# NanoPiAir_SDR_Shield_V1.net
KiCad netlist of a schematic drawn in Altium Designer
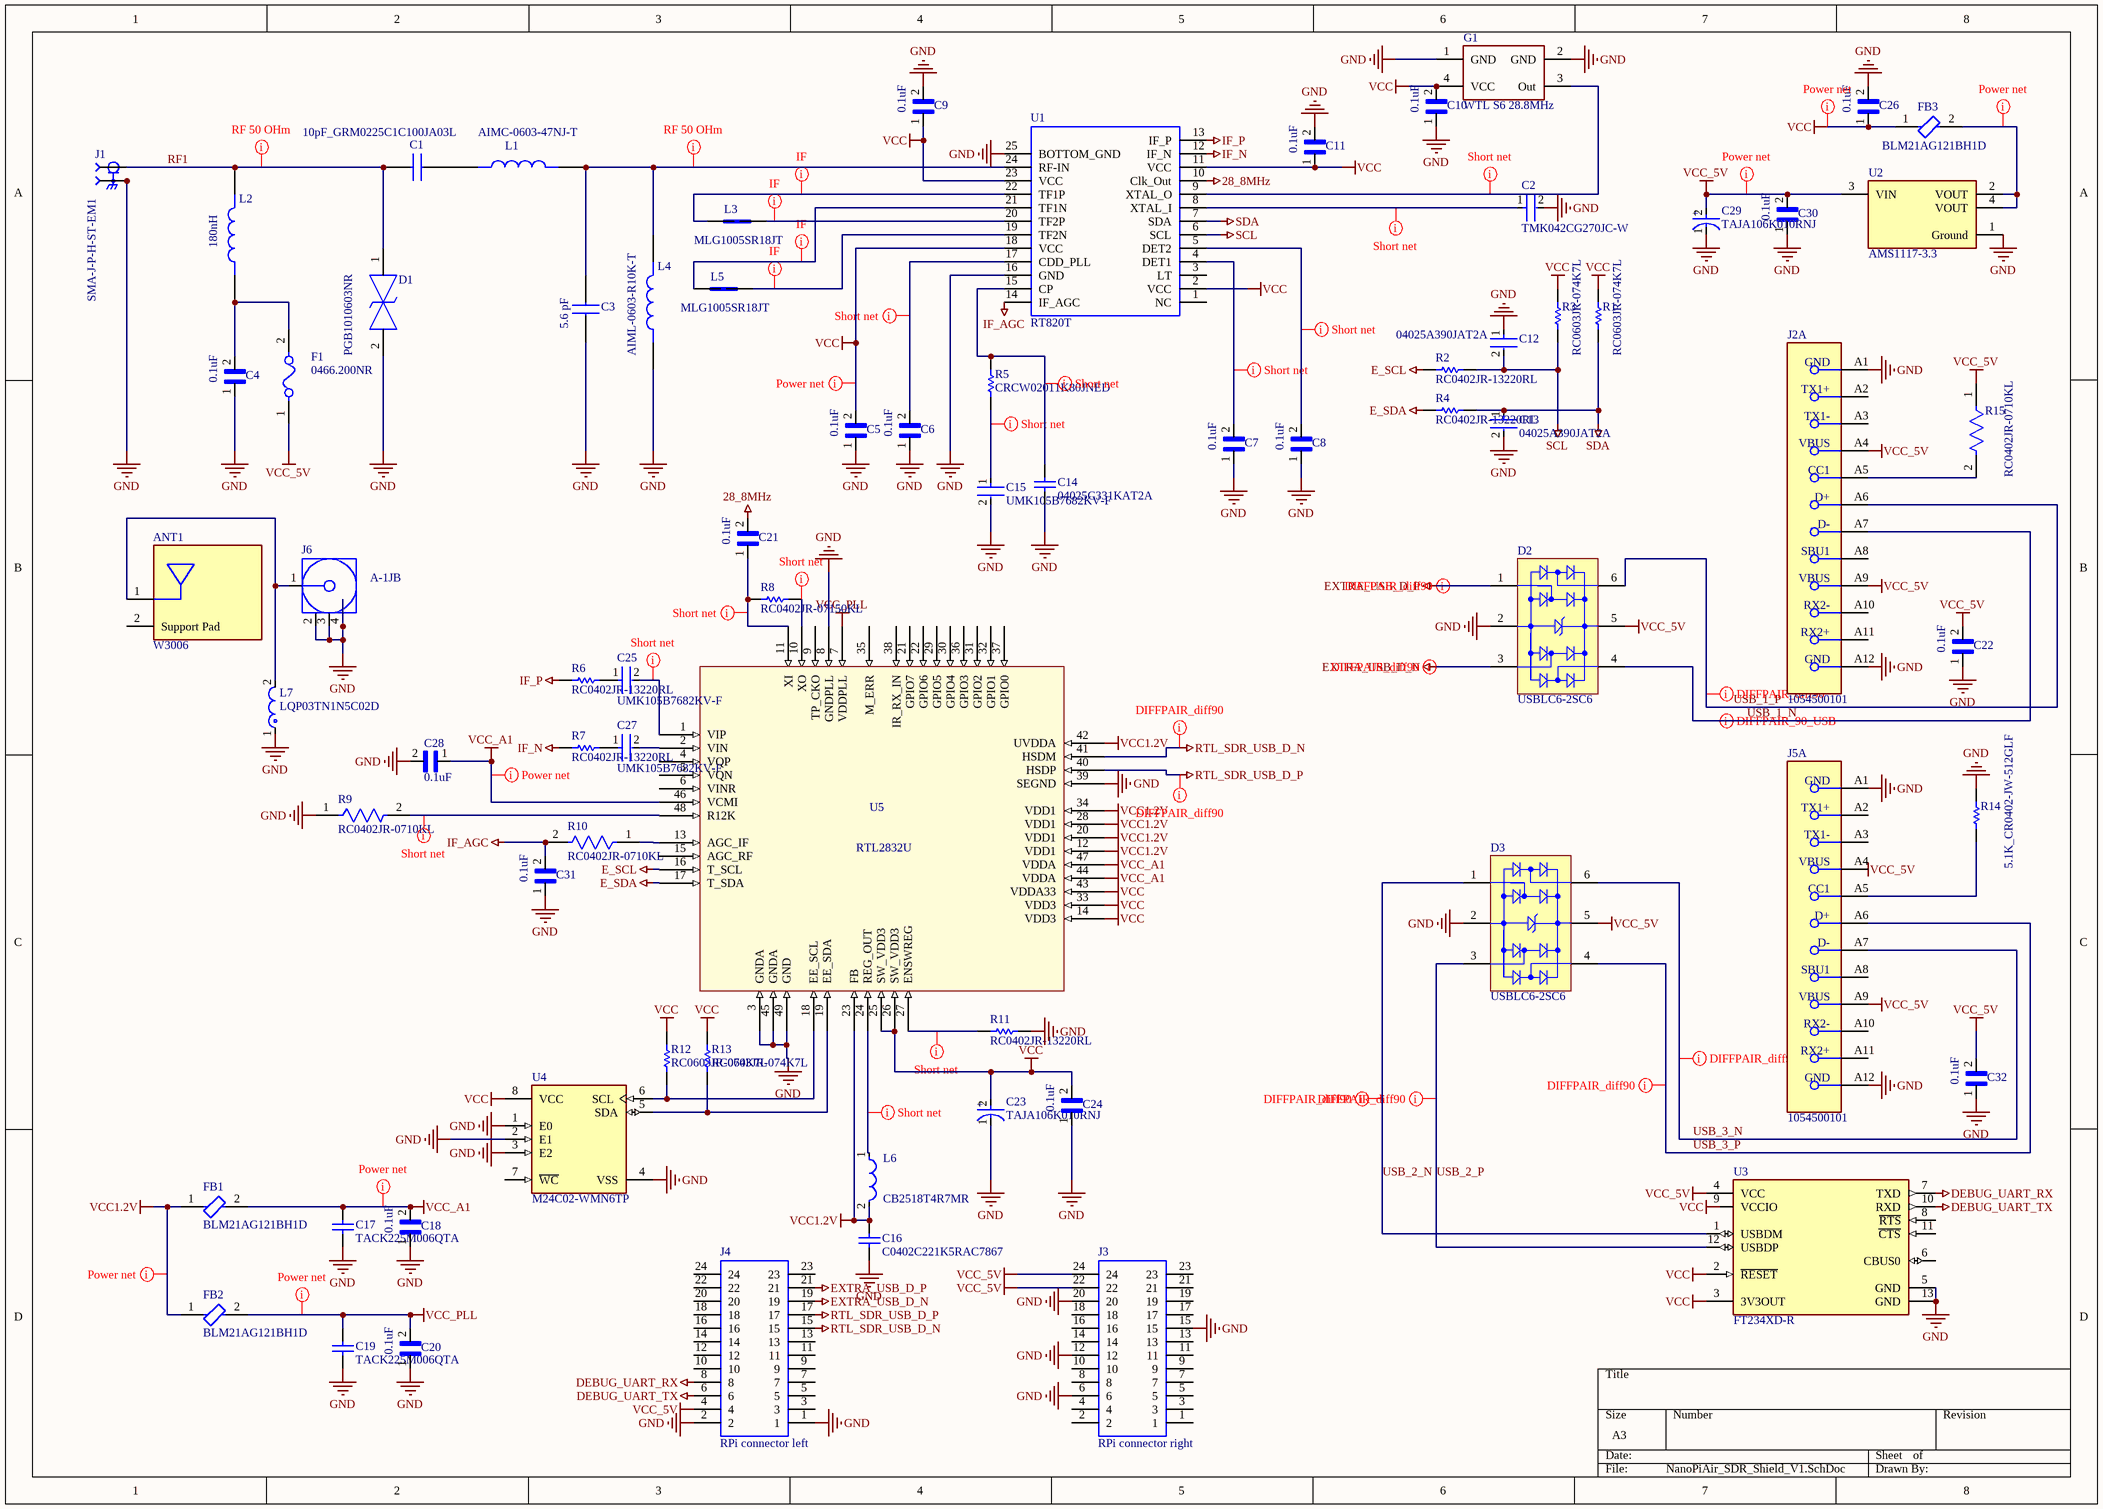
[diagram p0: NanoPiAir_SDR_Shield_V1.SchDoc]

(export (version "E")
  (design (tool "Eeschema 10.0.6"))
  (components
    (comp (ref "ANT1")
      (value "W3006")
      (footprint "FP-W3006-0")
      (description "RF ANT 2.4GHZ/5.5GHZ CHIP SLD")
      (libsource (lib "Altium Content Vault") (part "7e9f1c3ea5b015cef85830d8f377364"))
    )
    (comp (ref "C1")
      (value "10pF_GRM0225C1C100JA03L")
      (footprint "CAPC0402X22N")
      (description "Cap Ceramic 10pF 16V C0G 5% Pad SMD 01005 125C T/R")
      (fields
        (field (name "MOUSER PART NUMBER") "81-GRM0225C1C100JA3L")
        (field (name "MANUFACTURER_PART_NUMBER") "GRM0225C1C100JA03L")
      )
      (libsource (lib "Schlib1") (part "GRM0225C1C100JA03L"))
    )
    (comp (ref "C2")
      (value "TMK042CG270JC-W")
      (footprint "FP-01005-L_0_4_0_02-W_0_2-MFG")
      (description "None")
      (libsource (lib "Schlib1") (part "CMP-14477-000467-2"))
    )
    (comp (ref "C3")
      (value "5.6 pF")
      (footprint "C0603")
      (fields
        (field (name "MOUSER PART NUMBER") "80-C0603C569C5G")
        (field (name "MANUFACTURER_PART_NUMBER") "C0603C569C5GACTU")
      )
      (libsource (lib "Schlib1") (part "C0603C569C5GACTU"))
    )
    (comp (ref "C4")
      (value "0.1uF")
      (footprint "CAPC1005X55N")
      (fields (field (name "MP") "LMF105B7104KVHF"))
      (libsource (lib "Schlib1") (part "LMF105B7104KVHF"))
    )
    (comp (ref "C5")
      (value "0.1uF")
      (footprint "CAPC1005X55N")
      (fields (field (name "MP") "LMF105B7104KVHF"))
      (libsource (lib "Schlib1") (part "LMF105B7104KVHF"))
    )
    (comp (ref "C6")
      (value "0.1uF")
      (footprint "CAPC1005X55N")
      (fields (field (name "MP") "LMF105B7104KVHF"))
      (libsource (lib "Schlib1") (part "LMF105B7104KVHF"))
    )
    (comp (ref "C7")
      (value "0.1uF")
      (footprint "CAPC1005X55N")
      (fields (field (name "MP") "LMF105B7104KVHF"))
      (libsource (lib "Schlib1") (part "LMF105B7104KVHF"))
    )
    (comp (ref "C8")
      (value "0.1uF")
      (footprint "CAPC1005X55N")
      (fields (field (name "MP") "LMF105B7104KVHF"))
      (libsource (lib "Schlib1") (part "LMF105B7104KVHF"))
    )
    (comp (ref "C9")
      (value "0.1uF")
      (footprint "CAPC1005X55N")
      (fields (field (name "MP") "LMF105B7104KVHF"))
      (libsource (lib "Schlib1") (part "LMF105B7104KVHF"))
    )
    (comp (ref "C10")
      (value "0.1uF")
      (footprint "CAPC1005X55N")
      (fields (field (name "MP") "LMF105B7104KVHF"))
      (libsource (lib "Schlib1") (part "LMF105B7104KVHF"))
    )
    (comp (ref "C11")
      (value "0.1uF")
      (footprint "CAPC1005X55N")
      (fields (field (name "MP") "LMF105B7104KVHF"))
      (libsource (lib "Schlib1") (part "LMF105B7104KVHF"))
    )
    (comp (ref "C12")
      (value "04025A390JAT2A")
      (footprint "FP-0402-L_1_0_1-W_0_5_0_1-IPC_B")
      (description "General Purpose Ceramic Capacitor, 0402, 39pF, 5%, C0G, 30ppm/°C, 50V")
      (fields (field (name "TOLERANCE") "5%") (field (name "VOLTAGE") "50V"))
      (libsource (lib "Altium Content Vault") (part "b4654b650e69147ec39a6b967a45e02"))
    )
    (comp (ref "C13")
      (value "04025A390JAT2A")
      (footprint "FP-0402-L_1_0_1-W_0_5_0_1-IPC_B")
      (description "General Purpose Ceramic Capacitor, 0402, 39pF, 5%, C0G, 30ppm/°C, 50V")
      (fields (field (name "TOLERANCE") "5%") (field (name "VOLTAGE") "50V"))
      (libsource (lib "Altium Content Vault") (part "b4654b650e69147ec39a6b967a45e02"))
    )
    (comp (ref "C14")
      (value "04025C331KAT2A")
      (footprint "CAPC1005X56X25NL10T15")
      (fields (field (name "MANUFACTURER") "AVX Interconnect / Elco"))
      (libsource (lib "Altium Content Vault") (part "CAP"))
    )
    (comp (ref "C15")
      (value "UMK105B7682KV-F")
      (footprint "FP-0402-L_1_0_0_05-W_0_5-IPC_C")
      (description "None")
      (fields (field (name "TOLERANCE") "10%") (field (name "VOLTAGE") "50V"))
      (libsource (lib "Altium Content Vault") (part "b4654b650e69147ec39a6b967a45e02"))
    )
    (comp (ref "C16")
      (value "C0402C221K5RAC7867")
      (footprint "CAPC1005X60X30NL05T10")
      (fields (field (name "MANUFACTURER") "Kemet"))
      (libsource (lib "Altium Content Vault") (part "CAP"))
    )
    (comp (ref "C17")
      (value "TACK225M006QTA")
      (footprint "CAPC1005X70X10NL20T00")
      (fields (field (name "MANUFACTURER") "AVX Interconnect / Elco"))
      (libsource (lib "Altium Content Vault") (part "CAP"))
    )
    (comp (ref "C18")
      (value "0.1uF")
      (footprint "CAPC1005X55N")
      (fields (field (name "MP") "LMF105B7104KVHF"))
      (libsource (lib "Schlib1") (part "LMF105B7104KVHF"))
    )
    (comp (ref "C19")
      (value "TACK225M006QTA")
      (footprint "CAPC1005X70X10NL20T00")
      (fields (field (name "MANUFACTURER") "AVX Interconnect / Elco"))
      (libsource (lib "Altium Content Vault") (part "CAP"))
    )
    (comp (ref "C20")
      (value "0.1uF")
      (footprint "CAPC1005X55N")
      (fields (field (name "MP") "LMF105B7104KVHF"))
      (libsource (lib "Schlib1") (part "LMF105B7104KVHF"))
    )
    (comp (ref "C21")
      (value "0.1uF")
      (footprint "CAPC1005X55N")
      (fields (field (name "MP") "LMF105B7104KVHF"))
      (libsource (lib "Schlib1") (part "LMF105B7104KVHF"))
    )
    (comp (ref "C22")
      (value "0.1uF")
      (footprint "CAPC1005X55N")
      (fields (field (name "MP") "LMF105B7104KVHF"))
      (libsource (lib "Schlib1") (part "LMF105B7104KVHF"))
    )
    (comp (ref "C23")
      (value "TAJA106K010RNJ")
      (footprint "FP-TAJA-MFG")
      (description "10uF 10V  ±10% 3Ω 1206  SMD Tantalum Capacitor")
      (fields (field (name "TOLERANCE") "10%") (field (name "VOLTAGE") "10V"))
      (libsource (lib "Altium Content Vault") (part "203bc49f2ac43e59fd269a8c329ed05"))
    )
    (comp (ref "C24")
      (value "0.1uF")
      (footprint "CAPC1005X55N")
      (fields (field (name "MP") "LMF105B7104KVHF"))
      (libsource (lib "Schlib1") (part "LMF105B7104KVHF"))
    )
    (comp (ref "C25")
      (value "UMK105B7682KV-F")
      (footprint "FP-0402-L_1_0_0_05-W_0_5-IPC_C")
      (description "None")
      (fields (field (name "TOLERANCE") "10%") (field (name "VOLTAGE") "50V"))
      (libsource (lib "Altium Content Vault") (part "b4654b650e69147ec39a6b967a45e02"))
    )
    (comp (ref "C26")
      (value "0.1uF")
      (footprint "CAPC1005X55N")
      (fields (field (name "MP") "LMF105B7104KVHF"))
      (libsource (lib "Schlib1") (part "LMF105B7104KVHF"))
    )
    (comp (ref "C27")
      (value "UMK105B7682KV-F")
      (footprint "FP-0402-L_1_0_0_05-W_0_5-IPC_C")
      (description "None")
      (fields (field (name "TOLERANCE") "10%") (field (name "VOLTAGE") "50V"))
      (libsource (lib "Altium Content Vault") (part "b4654b650e69147ec39a6b967a45e02"))
    )
    (comp (ref "C28")
      (value "0.1uF")
      (footprint "CAPC1005X55N")
      (fields (field (name "MP") "LMF105B7104KVHF"))
      (libsource (lib "") (part "LMF105B7104KVHF_1"))
    )
    (comp (ref "C29")
      (value "TAJA106K010RNJ")
      (footprint "FP-TAJA-MFG")
      (description "10uF 10V  ±10% 3Ω 1206  SMD Tantalum Capacitor")
      (fields (field (name "TOLERANCE") "10%") (field (name "VOLTAGE") "10V"))
      (libsource (lib "Altium Content Vault") (part "203bc49f2ac43e59fd269a8c329ed05"))
    )
    (comp (ref "C30")
      (value "0.1uF")
      (footprint "CAPC1005X55N")
      (fields (field (name "MP") "LMF105B7104KVHF"))
      (libsource (lib "Schlib1") (part "LMF105B7104KVHF"))
    )
    (comp (ref "C31")
      (value "0.1uF")
      (footprint "CAPC1005X55N")
      (fields (field (name "MP") "LMF105B7104KVHF"))
      (libsource (lib "Schlib1") (part "LMF105B7104KVHF"))
    )
    (comp (ref "C32")
      (value "0.1uF")
      (footprint "CAPC1005X55N")
      (fields (field (name "MP") "LMF105B7104KVHF"))
      (libsource (lib "Schlib1") (part "LMF105B7104KVHF"))
    )
    (comp (ref "D1")
      (value "PGB1010603NR")
      (footprint "PGB1010603MR")
      (description "ESD Suppressors / TVS Diodes 0603 24VDC .06pF")
      (fields (field (name "MOUSER PART NUMBER") "576-PGB1010603NR"))
      (libsource (lib "Schlib1") (part "PGB1010603NR"))
    )
    (comp (ref "D2")
      (value "USBLC6-2SC6")
      (footprint "STM-SOT23-6L_V")
      (description "Very low capacitance ESD protection, 3.5 pF, -40 to 125 degC, 6-Pin SOT23, RoHS, Tape and Reel")
      (fields (field (name "MANUFACTURER") "STMicroelectronics"))
      (libsource (lib "Altium Content Vault") (part "STM-USB_DVI_HDMIULC6-4SC6X-SOT23-6L"))
    )
    (comp (ref "D3")
      (value "USBLC6-2SC6")
      (footprint "STM-SOT23-6L_V")
      (description "Very low capacitance ESD protection, 3.5 pF, -40 to 125 degC, 6-Pin SOT23, RoHS, Tape and Reel")
      (fields (field (name "MANUFACTURER") "STMicroelectronics"))
      (libsource (lib "Altium Content Vault") (part "STM-USB_DVI_HDMIULC6-4SC6X-SOT23-6L"))
    )
    (comp (ref "F1")
      (value "0466.200NR")
      (footprint "FP-0466-MFG")
      (description "FUSE BOARD MNT 200MA 125VAC/VDC")
      (libsource (lib "Altium Content Vault") (part "5bcf9b9f640e542cf0359d10258e979"))
    )
    (comp (ref "FB1")
      (value "BLM21AG121BH1D")
      (footprint "FP-BLM21-0_2-t0_85-e0_5-IPC_B")
      (description "Chip Ferrite Bead, 0805, 120Ω @ 100MHz, 0.09Ω, 25%, 1A")
      (libsource (lib "Altium Content Vault") (part "5f30dd21d616792df468990f7003faa"))
    )
    (comp (ref "FB2")
      (value "BLM21AG121BH1D")
      (footprint "FP-BLM21-0_2-t0_85-e0_5-IPC_B")
      (description "Chip Ferrite Bead, 0805, 120Ω @ 100MHz, 0.09Ω, 25%, 1A")
      (libsource (lib "Altium Content Vault") (part "5f30dd21d616792df468990f7003faa"))
    )
    (comp (ref "FB3")
      (value "BLM21AG121BH1D")
      (footprint "FP-BLM21-0_2-t0_85-e0_5-IPC_B")
      (description "Chip Ferrite Bead, 0805, 120Ω @ 100MHz, 0.09Ω, 25%, 1A")
      (libsource (lib "Altium Content Vault") (part "5f30dd21d616792df468990f7003faa"))
    )
    (comp (ref "G1")
      (value "WTL S6 28.8MHz")
      (footprint "XTAL_RTL_SDR(CHINA_WTL_S6)")
      (description "28.2 MHz Â±1ppm Generator")
      (fields (field (name "MF") "ECS Inc.") (field (name "DIGI-KEY_PART_NUMBER") "XC2021-2-ND"))
      (libsource (lib "Schlib1") (part "WTL S6 28.8MHz"))
    )
    (comp (ref "J1")
      (value "SMA-J-P-H-ST-EM1")
      (footprint "SAMTEC_SMA-J-P-H-ST-EM1")
      (description "SMA Connector Jack, Female Socket 50Ohm Board Edge, End Launch Solder")
      (libsource (lib "Schlib1") (part "SMA-J-P-H-ST-EM1"))
    )
    (comp (ref "J2")
      (value "1054500101")
      (footprint "FP-1054500101-MFG")
      (description "CONN RCP USB3.1 TYPEC 24P SMD RA")
      (fields
        (field (name "MANUFACTURER") "Molex")
        (field (name "OCTOPART") "https://octopart.com/105450-0101-molex-68082325")
      )
      (libsource (lib "Altium Content Vault") (part "9808b19ecaf079fb99eed69f0495cd0"))
    )
    (comp (ref "J3")
      (value "RPi connector right")
      (footprint "RHDR24W77P254X254_2X12_3048X503X673P")
      (description "Headers & Wire Housings RECEPT 24POS .100 VERT DUAL")
      (fields
        (field (name "MOUSER PART NUMBER") "571-6-534998-2")
        (field (name "MANUFACTURER_PART_NUMBER") "6-534998-2")
      )
      (libsource (lib "Schlib1") (part "6-534998-2"))
    )
    (comp (ref "J4")
      (value "RPi connector left")
      (footprint "RHDR24W77P254X254_2X12_3048X503X673P")
      (description "Headers & Wire Housings RECEPT 24POS .100 VERT DUAL")
      (fields
        (field (name "MOUSER PART NUMBER") "571-6-534998-2")
        (field (name "MANUFACTURER_PART_NUMBER") "6-534998-2")
      )
      (libsource (lib "Schlib1") (part "6-534998-2"))
    )
    (comp (ref "J5")
      (value "1054500101")
      (footprint "FP-1054500101-MFG")
      (description "CONN RCP USB3.1 TYPEC 24P SMD RA")
      (fields
        (field (name "MANUFACTURER") "Molex")
        (field (name "OCTOPART") "https://octopart.com/105450-0101-molex-68082325")
      )
      (libsource (lib "Altium Content Vault") (part "9808b19ecaf079fb99eed69f0495cd0"))
    )
    (comp (ref "J6")
      (value "A-1JB")
      (footprint "AMPH-A-1JB_V")
      (description "AMC PCB Jack, 0 to 60 GHz, 60 V, -40 to 90 degC, 4-Pin SMD, RoHS, Tape and Reel")
      (fields (field (name "TOLERANCE") "10%"))
      (libsource (lib "Altium Content Vault") (part "CN-S-3F-RF4"))
    )
    (comp (ref "L1")
      (value "AIMC-0603-47NJ-T")
      (footprint "INDC1608X95N")
      (description "IND 47nH 0.3A 700mâ„¦")
      (fields (field (name "MF") "Abracon"))
      (libsource (lib "Schlib1") (part "AIMC-0603-47NJ-T"))
    )
    (comp (ref "L2")
      (value "180nH")
      (footprint "INDC1608X95N")
      (description "IND 0.18uH 0.05A 600mâ„¦")
      (fields (field (name "MP") "AIML-0603-R18K-T") (field (name "MF") "Abracon"))
      (libsource (lib "Schlib1") (part "AIML-0603-R18K-T"))
    )
    (comp (ref "L3")
      (value "MLG1005SR18JT")
      (footprint "CAPC1005X55N")
      (description "Ind High Frequency Chip Unshielded Multi-Layer 180nH 5% 100MHz 8Q-Factor Ceramic 150mA 0402 T/R")
      (libsource (lib "Schlib1") (part "MLG1005SR18JT"))
    )
    (comp (ref "L4")
      (value "AIML-0603-R10K-T")
      (footprint "INDC1608X95N")
      (description "100 nH Shielded Multilayer Inductor 50 mA 500mOhm Max 0603 (1608 Metric)")
      (fields (field (name "MF") "Abracon"))
      (libsource (lib "Schlib1") (part "AIML-0603-R10K-T"))
    )
    (comp (ref "L5")
      (value "MLG1005SR18JT")
      (footprint "CAPC1005X55N")
      (description "Ind High Frequency Chip Unshielded Multi-Layer 180nH 5% 100MHz 8Q-Factor Ceramic 150mA 0402 T/R")
      (libsource (lib "Schlib1") (part "MLG1005SR18JT"))
    )
    (comp (ref "L6")
      (value "CB2518T4R7MR")
      (footprint "FP-CB2518-IPC_B")
      (description "SMD Inductors 4.7uH ±20% 1.2A 0.13Ω 1007")
      (fields (field (name "TOLERANCE") "20%"))
      (libsource (lib "Altium Content Vault") (part "725321dda6339637d4d059423bc1c3c"))
    )
    (comp (ref "L7")
      (value "LQP03TN1N5C02D")
      (footprint "FP-LQP03TG_02-IPC_A")
      (description "Film type RF Inductor 1.5nH ±0.2nH 600mA 0.15Ω 0201 (0603)")
      (libsource (lib "Altium Content Vault") (part "4cc4b267dca4c8e51f7102f422741d8"))
    )
    (comp (ref "R1")
      (value "RC0603JR-074K7L")
      (footprint "RESC1608X55X25ML10T15")
      (description "Chip Resistor, 4.7 KOhm, +/- 5%, 100 mW, -55 to 155 degC, 0603 (1608 Metric), RoHS, Tape and Reel")
      (fields (field (name "TOLERANCE") "5%") (field (name "MANUFACTURER") "Yageo"))
      (libsource (lib "Altium Content Vault") (part "RES-2"))
    )
    (comp (ref "R2")
      (value "RC0402JR-13220RL")
      (footprint "RESC1005X40X25ML05T10")
      (fields (field (name "MANUFACTURER") "Yageo"))
      (libsource (lib "Altium Content Vault") (part "RES"))
    )
    (comp (ref "R3")
      (value "RC0603JR-074K7L")
      (footprint "RESC1608X55X25ML10T15")
      (description "Chip Resistor, 4.7 KOhm, +/- 5%, 100 mW, -55 to 155 degC, 0603 (1608 Metric), RoHS, Tape and Reel")
      (fields (field (name "TOLERANCE") "5%") (field (name "MANUFACTURER") "Yageo"))
      (libsource (lib "Altium Content Vault") (part "RES-2"))
    )
    (comp (ref "R4")
      (value "RC0402JR-13220RL")
      (footprint "RESC1005X40X25ML05T10")
      (fields (field (name "MANUFACTURER") "Yageo"))
      (libsource (lib "Altium Content Vault") (part "RES"))
    )
    (comp (ref "R5")
      (value "CRCW02011K80JNED")
      (footprint "RESC0603X28X15LL05T05")
      (fields (field (name "MANUFACTURER") "Vishay Dale"))
      (libsource (lib "Altium Content Vault") (part "RES"))
    )
    (comp (ref "R6")
      (value "RC0402JR-13220RL")
      (footprint "RESC1005X40X25ML05T10")
      (fields (field (name "MANUFACTURER") "Yageo"))
      (libsource (lib "Altium Content Vault") (part "RES"))
    )
    (comp (ref "R7")
      (value "RC0402JR-13220RL")
      (footprint "RESC1005X40X25ML05T10")
      (fields (field (name "MANUFACTURER") "Yageo"))
      (libsource (lib "Altium Content Vault") (part "RES"))
    )
    (comp (ref "R8")
      (value "RC0402JR-07150KL")
      (footprint "RESC1005X40X25ML05T10")
      (fields (field (name "MANUFACTURER") "Yageo / Phycomp"))
      (libsource (lib "Altium Content Vault") (part "RES"))
    )
    (comp (ref "R9")
      (value "RC0402JR-0710KL")
      (footprint "FP-RC0402-0_4-IPC_C")
      (description "RES 10K OHM 5% 1/16W 0402")
      (fields (field (name "TOLERANCE") "5%"))
      (libsource (lib "Altium Content Vault") (part "1029c3af85768c4190bb7ad29bc67b5"))
    )
    (comp (ref "R10")
      (value "RC0402JR-0710KL")
      (footprint "FP-RC0402-0_4-IPC_C")
      (description "RES 10K OHM 5% 1/16W 0402")
      (fields (field (name "TOLERANCE") "5%"))
      (libsource (lib "Altium Content Vault") (part "1029c3af85768c4190bb7ad29bc67b5"))
    )
    (comp (ref "R11")
      (value "RC0402JR-13220RL")
      (footprint "RESC1005X40X25ML05T10")
      (fields (field (name "MANUFACTURER") "Yageo"))
      (libsource (lib "Altium Content Vault") (part "RES"))
    )
    (comp (ref "R12")
      (value "RC0603JR-074K7L")
      (footprint "RESC1608X55X25ML10T15")
      (description "Chip Resistor, 4.7 KOhm, +/- 5%, 100 mW, -55 to 155 degC, 0603 (1608 Metric), RoHS, Tape and Reel")
      (fields (field (name "TOLERANCE") "5%") (field (name "MANUFACTURER") "Yageo"))
      (libsource (lib "Altium Content Vault") (part "RES-2"))
    )
    (comp (ref "R13")
      (value "RC0603JR-074K7L")
      (footprint "RESC1608X55X25ML10T15")
      (description "Chip Resistor, 4.7 KOhm, +/- 5%, 100 mW, -55 to 155 degC, 0603 (1608 Metric), RoHS, Tape and Reel")
      (fields (field (name "TOLERANCE") "5%") (field (name "MANUFACTURER") "Yageo"))
      (libsource (lib "Altium Content Vault") (part "RES-2"))
    )
    (comp (ref "R14")
      (value "5.1K_CR0402-JW-512GLF")
      (footprint "RESC1005X40X25LL10T10")
      (fields (field (name "PART NUMBER") "CR0402-JW-512GLF") (field (name "MANUFACTURER") "Bourns"))
      (libsource (lib "Altium Content Vault") (part "RES"))
    )
    (comp (ref "R15")
      (value "RC0402JR-0710KL")
      (footprint "FP-RC0402-0_4-IPC_C")
      (description "RES 10K OHM 5% 1/16W 0402")
      (fields (field (name "TOLERANCE") "5%"))
      (libsource (lib "Altium Content Vault") (part "1029c3af85768c4190bb7ad29bc67b5"))
    )
    (comp (ref "U1")
      (value "RT820T")
      (footprint "EFM8LB12F64ES0BQFN24")
      (description "High Performance Low Power\r\nAdvanced Digital TV Silicon Tuner")
      (libsource (lib "Schlib1") (part "RT820T-QFN24"))
    )
    (comp (ref "U2")
      (value "AMS1117-3.3")
      (footprint "FP-AMS1117-IPC_C")
      (description "LDO Voltage Regulators 1A, 3.3V")
      (fields
        (field (name "OCTOPART") "https://octopart.com/ams1117-3.3-advanced+monolithic+systems-25899300")
        (field (name "MANUFACTURER") "Advanced Monolithic Systems")
      )
      (libsource (lib "Altium Content Vault") (part "8bdbb5f8e77002000e30dd2845d0354"))
    )
    (comp (ref "U3")
      (value "FT234XD-R")
      (footprint "FP-DFN-12-IPC_B")
      (description "IC USB SERIAL BASIC UART 12DFN")
      (libsource (lib "Altium Content Vault") (part "4bef3367ed9f9051bcb84ab46edda1c"))
    )
    (comp (ref "U4")
      (value "M24C02-WMN6TP")
      (footprint "FP-SO8N-SO-A-MFG")
      (description "IC EEPROM 2K I2C 400KHZ 8SO")
      (fields
        (field (name "MANUFACTURER") "STMicroelectronics")
        (field (name "OCTOPART") "https://octopart.com/m24c02-wmn6tp-stmicroelectronics-55404516")
      )
      (libsource (lib "Altium Content Vault") (part "6c91e1c1613830ec3abd94c18390ae3"))
    )
    (comp (ref "U5")
      (value "RTL2832U")
      (footprint "QFN40P600X600X84_HS-49N")
      (description "RTL2832U DVB-T COFDM Demodulator + USB 2.0")
      (fields (field (name "MANUFACTURER") "Realtek") (field (name "PUBLISHER") "ftg"))
      (libsource (lib "Schlib1") (part "RTL2832U"))
    )
  )
  (nets
    (net (code "1") (name "/RF1") (class "Default")
      (node (ref "C1") (pin "1") (pinfunction "1_1") (pintype "passive"))
      (node (ref "D1") (pin "1") (pinfunction "1_1") (pintype "passive"))
      (node (ref "J1") (pin "1") (pinfunction "1_1") (pintype "passive"))
      (node (ref "L2") (pin "2") (pinfunction "2_2") (pintype "passive"))
    )
    (net (code "2") (name "/USB_1_N") (class "Default")
      (node (ref "D2") (pin "4") (pinfunction "I/O_3_4") (pintype "passive"))
      (node (ref "J2") (pin "A7") (pinfunction "D-_A7") (pintype "passive"))
    )
    (net (code "3") (name "/USB_1_P") (class "Default")
      (node (ref "D2") (pin "6") (pinfunction "I/O_4_6") (pintype "passive"))
      (node (ref "J2") (pin "A6") (pinfunction "D+_A6") (pintype "passive"))
    )
    (net (code "4") (name "/USB_2_N") (class "Default")
      (node (ref "D3") (pin "1") (pinfunction "I/O_1_1") (pintype "passive"))
      (node (ref "U3") (pin "1") (pinfunction "USBDM_1") (pintype "bidirectional"))
    )
    (net (code "5") (name "/USB_2_P") (class "Default")
      (node (ref "D3") (pin "3") (pinfunction "I/O_2_3") (pintype "passive"))
      (node (ref "U3") (pin "12") (pinfunction "USBDP_12") (pintype "bidirectional"))
    )
    (net (code "6") (name "/USB_3_N") (class "Default")
      (node (ref "D3") (pin "6") (pinfunction "I/O_4_6") (pintype "passive"))
      (node (ref "J5") (pin "A7") (pinfunction "D-_A7") (pintype "passive"))
    )
    (net (code "7") (name "/USB_3_P") (class "Default")
      (node (ref "D3") (pin "4") (pinfunction "I/O_3_4") (pintype "passive"))
      (node (ref "J5") (pin "A6") (pinfunction "D+_A6") (pintype "passive"))
    )
    (net (code "8") (name "28_8MHz") (class "Default")
      (node (ref "C21") (pin "2") (pinfunction "2_2") (pintype "passive"))
      (node (ref "U1") (pin "10") (pinfunction "Clk_Out_10") (pintype "passive"))
    )
    (net (code "9") (name "DEBUG_UART_RX") (class "Default")
      (node (ref "J4") (pin "8") (pinfunction "8_8") (pintype "passive"))
      (node (ref "U3") (pin "7") (pinfunction "TXD_7") (pintype "output"))
    )
    (net (code "10") (name "DEBUG_UART_TX") (class "Default")
      (node (ref "J4") (pin "6") (pinfunction "6_6") (pintype "passive"))
      (node (ref "U3") (pin "10") (pinfunction "RXD_10") (pintype "output"))
    )
    (net (code "11") (name "EXTRA_USB_D_N") (class "Default")
      (node (ref "D2") (pin "3") (pinfunction "I/O_2_3") (pintype "passive"))
      (node (ref "J4") (pin "19") (pinfunction "19_19") (pintype "passive"))
    )
    (net (code "12") (name "EXTRA_USB_D_P") (class "Default")
      (node (ref "D2") (pin "1") (pinfunction "I/O_1_1") (pintype "passive"))
      (node (ref "J4") (pin "21") (pinfunction "21_21") (pintype "passive"))
    )
    (net (code "13") (name "E_SCL") (class "Default")
      (node (ref "R2") (pin "1") (pinfunction "1_1") (pintype "passive"))
      (node (ref "U5") (pin "16") (pinfunction "T_SCL_16") (pintype "input"))
    )
    (net (code "14") (name "E_SDA") (class "Default")
      (node (ref "R4") (pin "1") (pinfunction "1_1") (pintype "passive"))
      (node (ref "U5") (pin "17") (pinfunction "T_SDA_17") (pintype "input"))
    )
    (net (code "15") (name "GND") (class "Default")
      (node (ref "C10") (pin "1") (pinfunction "1_1") (pintype "passive"))
      (node (ref "C11") (pin "2") (pinfunction "2_2") (pintype "passive"))
      (node (ref "C12") (pin "1") (pinfunction "1_1") (pintype "passive"))
      (node (ref "C13") (pin "2") (pinfunction "2_2") (pintype "passive"))
      (node (ref "C14") (pin "1") (pinfunction "1_1") (pintype "passive"))
      (node (ref "C15") (pin "2") (pinfunction "2_2") (pintype "passive"))
      (node (ref "C16") (pin "1") (pinfunction "1_1") (pintype "passive"))
      (node (ref "C17") (pin "1") (pinfunction "1_1") (pintype "passive"))
      (node (ref "C18") (pin "1") (pinfunction "1_1") (pintype "passive"))
      (node (ref "C19") (pin "1") (pinfunction "1_1") (pintype "passive"))
      (node (ref "C2") (pin "2") (pinfunction "2_2") (pintype "passive"))
      (node (ref "C20") (pin "1") (pinfunction "1_1") (pintype "passive"))
      (node (ref "C22") (pin "1") (pinfunction "1_1") (pintype "passive"))
      (node (ref "C23") (pin "1") (pinfunction "C_1") (pintype "passive"))
      (node (ref "C24") (pin "1") (pinfunction "1_1") (pintype "passive"))
      (node (ref "C26") (pin "2") (pinfunction "2_2") (pintype "passive"))
      (node (ref "C28") (pin "2") (pinfunction "2_2") (pintype "passive"))
      (node (ref "C29") (pin "1") (pinfunction "C_1") (pintype "passive"))
      (node (ref "C3") (pin "1") (pinfunction "1_1") (pintype "passive"))
      (node (ref "C30") (pin "1") (pinfunction "1_1") (pintype "passive"))
      (node (ref "C31") (pin "1") (pinfunction "1_1") (pintype "passive"))
      (node (ref "C32") (pin "1") (pinfunction "1_1") (pintype "passive"))
      (node (ref "C4") (pin "1") (pinfunction "1_1") (pintype "passive"))
      (node (ref "C5") (pin "1") (pinfunction "1_1") (pintype "passive"))
      (node (ref "C6") (pin "1") (pinfunction "1_1") (pintype "passive"))
      (node (ref "C7") (pin "1") (pinfunction "1_1") (pintype "passive"))
      (node (ref "C8") (pin "1") (pinfunction "1_1") (pintype "passive"))
      (node (ref "C9") (pin "2") (pinfunction "2_2") (pintype "passive"))
      (node (ref "D1") (pin "2") (pinfunction "2_2") (pintype "passive"))
      (node (ref "D2") (pin "2") (pinfunction "GND_2") (pintype "passive"))
      (node (ref "D3") (pin "2") (pinfunction "GND_2") (pintype "passive"))
      (node (ref "G1") (pin "1") (pinfunction "GND_1") (pintype "passive"))
      (node (ref "G1") (pin "2") (pinfunction "GND_2") (pintype "passive"))
      (node (ref "J1") (pin "2_1") (pinfunction "2_2_1") (pintype "passive"))
      (node (ref "J1") (pin "2_2") (pinfunction "2_2_2") (pintype "passive"))
      (node (ref "J1") (pin "3_1") (pinfunction "2_3_1") (pintype "passive"))
      (node (ref "J1") (pin "3_2") (pinfunction "2_3_2") (pintype "passive"))
      (node (ref "J2") (pin "A1") (pinfunction "GND_A1") (pintype "passive"))
      (node (ref "J2") (pin "A12") (pinfunction "GND_A12") (pintype "passive"))
      (node (ref "J3") (pin "12") (pinfunction "12_12") (pintype "passive"))
      (node (ref "J3") (pin "15") (pinfunction "15_15") (pintype "passive"))
      (node (ref "J3") (pin "20") (pinfunction "20_20") (pintype "passive"))
      (node (ref "J3") (pin "6") (pinfunction "6_6") (pintype "passive"))
      (node (ref "J4") (pin "1") (pinfunction "1_1") (pintype "passive"))
      (node (ref "J4") (pin "2") (pinfunction "2_2") (pintype "passive"))
      (node (ref "J5") (pin "A1") (pinfunction "GND_A1") (pintype "passive"))
      (node (ref "J5") (pin "A12") (pinfunction "GND_A12") (pintype "passive"))
      (node (ref "J6") (pin "2") (pinfunction "2_2") (pintype "passive"))
      (node (ref "J6") (pin "3") (pinfunction "3_3") (pintype "passive"))
      (node (ref "J6") (pin "4") (pinfunction "4_4") (pintype "passive"))
      (node (ref "L4") (pin "1") (pinfunction "1_1") (pintype "passive"))
      (node (ref "L7") (pin "1") (pinfunction "1_1") (pintype "passive"))
      (node (ref "R11") (pin "2") (pinfunction "2_2") (pintype "passive"))
      (node (ref "R14") (pin "2") (pinfunction "2_2") (pintype "passive"))
      (node (ref "R9") (pin "1") (pinfunction "1_1") (pintype "passive"))
      (node (ref "U1") (pin "16") (pinfunction "GND_16") (pintype "passive"))
      (node (ref "U1") (pin "25") (pinfunction "BOTTOM_GND_25") (pintype "passive"))
      (node (ref "U2") (pin "1") (pinfunction "Ground_1") (pintype "power_in"))
      (node (ref "U3") (pin "13") (pinfunction "GND_13") (pintype "power_in"))
      (node (ref "U3") (pin "5") (pinfunction "GND_5") (pintype "power_in"))
      (node (ref "U4") (pin "1") (pinfunction "E0_1") (pintype "input"))
      (node (ref "U4") (pin "2") (pinfunction "E1_2") (pintype "input"))
      (node (ref "U4") (pin "3") (pinfunction "E2_3") (pintype "input"))
      (node (ref "U4") (pin "4") (pinfunction "VSS_4") (pintype "power_in"))
      (node (ref "U5") (pin "3") (pinfunction "GNDA_3") (pintype "input"))
      (node (ref "U5") (pin "39") (pinfunction "SEGND_39") (pintype "input"))
      (node (ref "U5") (pin "45") (pinfunction "GNDA_45") (pintype "input"))
      (node (ref "U5") (pin "49") (pinfunction "GND_49") (pintype "input"))
      (node (ref "U5") (pin "8") (pinfunction "GNDPLL_8") (pintype "input"))
    )
    (net (code "16") (name "IF_AGC") (class "Default")
      (node (ref "C31") (pin "2") (pinfunction "2_2") (pintype "passive"))
      (node (ref "R10") (pin "2") (pinfunction "2_2") (pintype "passive"))
      (node (ref "U1") (pin "14") (pinfunction "IF_AGC_14") (pintype "passive"))
    )
    (net (code "17") (name "IF_N") (class "Default")
      (node (ref "R7") (pin "1") (pinfunction "1_1") (pintype "passive"))
      (node (ref "U1") (pin "12") (pinfunction "IF_N_12") (pintype "passive"))
    )
    (net (code "18") (name "IF_P") (class "Default")
      (node (ref "R6") (pin "1") (pinfunction "1_1") (pintype "passive"))
      (node (ref "U1") (pin "13") (pinfunction "IF_P_13") (pintype "passive"))
    )
    (net (code "19") (name "Net-(ANT1-Feed)") (class "Default")
      (node (ref "ANT1") (pin "1") (pinfunction "Feed_1") (pintype "passive"))
      (node (ref "J6") (pin "1") (pinfunction "1_1") (pintype "passive"))
      (node (ref "L7") (pin "2") (pinfunction "2_2") (pintype "passive"))
    )
    (net (code "20") (name "Net-(C1-Pad2)") (class "Default")
      (node (ref "C1") (pin "2") (pinfunction "2_2") (pintype "passive"))
      (node (ref "L1") (pin "1") (pinfunction "1_1") (pintype "passive"))
    )
    (net (code "21") (name "Net-(C4-Pad2)") (class "Default")
      (node (ref "C4") (pin "2") (pinfunction "2_2") (pintype "passive"))
      (node (ref "F1") (pin "2") (pinfunction "2_2") (pintype "passive"))
      (node (ref "L2") (pin "1") (pinfunction "1_1") (pintype "passive"))
    )
    (net (code "22") (name "Net-(C15-Pad1)") (class "Default")
      (node (ref "C15") (pin "1") (pinfunction "1_1") (pintype "passive"))
      (node (ref "R5") (pin "1") (pinfunction "1_1") (pintype "passive"))
    )
    (net (code "23") (name "Net-(C25-Pad1)") (class "Default")
      (node (ref "C25") (pin "1") (pinfunction "1_1") (pintype "passive"))
      (node (ref "R6") (pin "2") (pinfunction "2_2") (pintype "passive"))
    )
    (net (code "24") (name "Net-(C27-Pad1)") (class "Default")
      (node (ref "C27") (pin "1") (pinfunction "1_1") (pintype "passive"))
      (node (ref "R7") (pin "2") (pinfunction "2_2") (pintype "passive"))
    )
    (net (code "25") (name "Net-(FB3-Pad2)") (class "Default")
      (node (ref "FB3") (pin "2") (pinfunction "2_2") (pintype "passive"))
      (node (ref "U2") (pin "2") (pinfunction "VOUT_2") (pintype "passive"))
      (node (ref "U2") (pin "4") (pinfunction "VOUT_4") (pintype "passive"))
    )
    (net (code "26") (name "Net-(G1-Out)") (class "Default")
      (node (ref "G1") (pin "3") (pinfunction "Out_3") (pintype "passive"))
      (node (ref "U1") (pin "9") (pinfunction "XTAL_O_9") (pintype "passive"))
    )
    (net (code "27") (name "Net-(J2A-CC1)") (class "Default")
      (node (ref "J2") (pin "A5") (pinfunction "CC1_A5") (pintype "passive"))
      (node (ref "R15") (pin "2") (pinfunction "2_2") (pintype "passive"))
    )
    (net (code "28") (name "Net-(J5A-CC1)") (class "Default")
      (node (ref "J5") (pin "A5") (pinfunction "CC1_A5") (pintype "passive"))
      (node (ref "R14") (pin "1") (pinfunction "1_1") (pintype "passive"))
    )
    (net (code "29") (name "Net-(U1-CDD_PLL)") (class "Default")
      (node (ref "C6") (pin "2") (pinfunction "2_2") (pintype "passive"))
      (node (ref "U1") (pin "17") (pinfunction "CDD_PLL_17") (pintype "passive"))
    )
    (net (code "30") (name "Net-(U1-CP)") (class "Default")
      (node (ref "C14") (pin "2") (pinfunction "2_2") (pintype "passive"))
      (node (ref "R5") (pin "2") (pinfunction "2_2") (pintype "passive"))
      (node (ref "U1") (pin "15") (pinfunction "CP_15") (pintype "passive"))
    )
    (net (code "31") (name "Net-(U1-DET1)") (class "Default")
      (node (ref "C7") (pin "2") (pinfunction "2_2") (pintype "passive"))
      (node (ref "U1") (pin "4") (pinfunction "DET1_4") (pintype "passive"))
    )
    (net (code "32") (name "Net-(U1-DET2)") (class "Default")
      (node (ref "C8") (pin "2") (pinfunction "2_2") (pintype "passive"))
      (node (ref "U1") (pin "5") (pinfunction "DET2_5") (pintype "passive"))
    )
    (net (code "33") (name "Net-(U1-RF-IN)") (class "Default")
      (node (ref "C3") (pin "2") (pinfunction "2_2") (pintype "passive"))
      (node (ref "L1") (pin "2") (pinfunction "2_2") (pintype "passive"))
      (node (ref "L4") (pin "2") (pinfunction "2_2") (pintype "passive"))
      (node (ref "U1") (pin "24") (pinfunction "RF-IN_24") (pintype "passive"))
    )
    (net (code "34") (name "Net-(U1-TF1N)") (class "Default")
      (node (ref "L5") (pin "1") (pinfunction "1_1") (pintype "passive"))
      (node (ref "U1") (pin "21") (pinfunction "TF1N_21") (pintype "passive"))
    )
    (net (code "35") (name "Net-(U1-TF1P)") (class "Default")
      (node (ref "L3") (pin "1") (pinfunction "1_1") (pintype "passive"))
      (node (ref "U1") (pin "22") (pinfunction "TF1P_22") (pintype "passive"))
    )
    (net (code "36") (name "Net-(U1-TF2N)") (class "Default")
      (node (ref "L5") (pin "2") (pinfunction "2_2") (pintype "passive"))
      (node (ref "U1") (pin "19") (pinfunction "TF2N_19") (pintype "passive"))
    )
    (net (code "37") (name "Net-(U1-TF2P)") (class "Default")
      (node (ref "L3") (pin "2") (pinfunction "2_2") (pintype "passive"))
      (node (ref "U1") (pin "20") (pinfunction "TF2P_20") (pintype "passive"))
    )
    (net (code "38") (name "Net-(U1-XTAL_I)") (class "Default")
      (node (ref "C2") (pin "1") (pinfunction "1_1") (pintype "passive"))
      (node (ref "U1") (pin "8") (pinfunction "XTAL_I_8") (pintype "passive"))
    )
    (net (code "39") (name "Net-(U4-SCL)") (class "Default")
      (node (ref "R12") (pin "2") (pinfunction "2_2") (pintype "passive"))
      (node (ref "U4") (pin "6") (pinfunction "SCL_6") (pintype "input"))
      (node (ref "U5") (pin "18") (pinfunction "EE_SCL_18") (pintype "input"))
    )
    (net (code "40") (name "Net-(U4-SDA)") (class "Default")
      (node (ref "R13") (pin "2") (pinfunction "2_2") (pintype "passive"))
      (node (ref "U4") (pin "5") (pinfunction "SDA_5") (pintype "bidirectional"))
      (node (ref "U5") (pin "19") (pinfunction "EE_SDA_19") (pintype "input"))
    )
    (net (code "41") (name "Net-(U5-AGC_IF)") (class "Default")
      (node (ref "R10") (pin "1") (pinfunction "1_1") (pintype "passive"))
      (node (ref "U5") (pin "13") (pinfunction "AGC_IF_13") (pintype "input"))
    )
    (net (code "42") (name "Net-(U5-ENSWREG)") (class "Default")
      (node (ref "R11") (pin "1") (pinfunction "1_1") (pintype "passive"))
      (node (ref "U5") (pin "27") (pinfunction "ENSWREG_27") (pintype "input"))
    )
    (net (code "43") (name "Net-(U5-R12K)") (class "Default")
      (node (ref "R9") (pin "2") (pinfunction "2_2") (pintype "passive"))
      (node (ref "U5") (pin "48") (pinfunction "R12K_48") (pintype "input"))
    )
    (net (code "44") (name "Net-(U5-REG_OUT)") (class "Default")
      (node (ref "L6") (pin "1") (pinfunction "1_1") (pintype "passive"))
      (node (ref "U5") (pin "24") (pinfunction "REG_OUT_24") (pintype "input"))
    )
    (net (code "45") (name "Net-(U5-VIN)") (class "Default")
      (node (ref "C27") (pin "2") (pinfunction "2_2") (pintype "passive"))
      (node (ref "U5") (pin "2") (pinfunction "VIN_2") (pintype "input"))
    )
    (net (code "46") (name "Net-(U5-VIP)") (class "Default")
      (node (ref "C25") (pin "2") (pinfunction "2_2") (pintype "passive"))
      (node (ref "U5") (pin "1") (pinfunction "VIP_1") (pintype "input"))
    )
    (net (code "47") (name "Net-(U5-XI)") (class "Default")
      (node (ref "C21") (pin "1") (pinfunction "1_1") (pintype "passive"))
      (node (ref "R8") (pin "2") (pinfunction "2_2") (pintype "passive"))
      (node (ref "U5") (pin "11") (pinfunction "XI_11") (pintype "input"))
    )
    (net (code "48") (name "Net-(U5-XO)") (class "Default")
      (node (ref "R8") (pin "1") (pinfunction "1_1") (pintype "passive"))
      (node (ref "U5") (pin "10") (pinfunction "XO_10") (pintype "input"))
    )
    (net (code "49") (name "RTL_SDR_USB_D_N") (class "Default")
      (node (ref "J4") (pin "15") (pinfunction "15_15") (pintype "passive"))
      (node (ref "U5") (pin "41") (pinfunction "HSDM_41") (pintype "input"))
    )
    (net (code "50") (name "RTL_SDR_USB_D_P") (class "Default")
      (node (ref "J4") (pin "17") (pinfunction "17_17") (pintype "passive"))
      (node (ref "U5") (pin "40") (pinfunction "HSDP_40") (pintype "input"))
    )
    (net (code "51") (name "SCL") (class "Default")
      (node (ref "C12") (pin "2") (pinfunction "2_2") (pintype "passive"))
      (node (ref "R2") (pin "2") (pinfunction "2_2") (pintype "passive"))
      (node (ref "R3") (pin "2") (pinfunction "2_2") (pintype "passive"))
      (node (ref "U1") (pin "6") (pinfunction "SCL_6") (pintype "passive"))
    )
    (net (code "52") (name "SDA") (class "Default")
      (node (ref "C13") (pin "1") (pinfunction "1_1") (pintype "passive"))
      (node (ref "R1") (pin "2") (pinfunction "2_2") (pintype "passive"))
      (node (ref "R4") (pin "2") (pinfunction "2_2") (pintype "passive"))
      (node (ref "U1") (pin "7") (pinfunction "SDA_7") (pintype "passive"))
    )
    (net (code "53") (name "VCC") (class "Default")
      (node (ref "C10") (pin "2") (pinfunction "2_2") (pintype "passive"))
      (node (ref "C11") (pin "1") (pinfunction "1_1") (pintype "passive"))
      (node (ref "C23") (pin "2") (pinfunction "A_2") (pintype "passive"))
      (node (ref "C24") (pin "2") (pinfunction "2_2") (pintype "passive"))
      (node (ref "C26") (pin "1") (pinfunction "1_1") (pintype "passive"))
      (node (ref "C5") (pin "2") (pinfunction "2_2") (pintype "passive"))
      (node (ref "C9") (pin "1") (pinfunction "1_1") (pintype "passive"))
      (node (ref "FB3") (pin "1") (pinfunction "1_1") (pintype "passive"))
      (node (ref "G1") (pin "4") (pinfunction "VCC_4") (pintype "passive"))
      (node (ref "R1") (pin "1") (pinfunction "1_1") (pintype "passive"))
      (node (ref "R12") (pin "1") (pinfunction "1_1") (pintype "passive"))
      (node (ref "R13") (pin "1") (pinfunction "1_1") (pintype "passive"))
      (node (ref "R3") (pin "1") (pinfunction "1_1") (pintype "passive"))
      (node (ref "U1") (pin "11") (pinfunction "VCC_11") (pintype "passive"))
      (node (ref "U1") (pin "18") (pinfunction "VCC_18") (pintype "passive"))
      (node (ref "U1") (pin "2") (pinfunction "VCC_2") (pintype "passive"))
      (node (ref "U1") (pin "23") (pinfunction "VCC_23") (pintype "passive"))
      (node (ref "U3") (pin "2") (pinfunction "~{RESET}_2") (pintype "input"))
      (node (ref "U3") (pin "3") (pinfunction "3V3OUT_3") (pintype "power_in"))
      (node (ref "U4") (pin "8") (pinfunction "VCC_8") (pintype "power_in"))
      (node (ref "U5") (pin "14") (pinfunction "VDD3_14") (pintype "input"))
      (node (ref "U5") (pin "25") (pinfunction "SW_VDD3_25") (pintype "input"))
      (node (ref "U5") (pin "26") (pinfunction "SW_VDD3_26") (pintype "input"))
      (node (ref "U5") (pin "33") (pinfunction "VDD3_33") (pintype "input"))
      (node (ref "U5") (pin "43") (pinfunction "VDDA33_43") (pintype "input"))
    )
    (net (code "54") (name "VCC1.2V") (class "Default")
      (node (ref "C16") (pin "2") (pinfunction "2_2") (pintype "passive"))
      (node (ref "FB1") (pin "1") (pinfunction "1_1") (pintype "passive"))
      (node (ref "FB2") (pin "1") (pinfunction "1_1") (pintype "passive"))
      (node (ref "L6") (pin "2") (pinfunction "2_2") (pintype "passive"))
      (node (ref "U5") (pin "12") (pinfunction "VDD1_12") (pintype "input"))
      (node (ref "U5") (pin "20") (pinfunction "VDD1_20") (pintype "input"))
      (node (ref "U5") (pin "23") (pinfunction "FB_23") (pintype "input"))
      (node (ref "U5") (pin "28") (pinfunction "VDD1_28") (pintype "input"))
      (node (ref "U5") (pin "34") (pinfunction "VDD1_34") (pintype "input"))
      (node (ref "U5") (pin "42") (pinfunction "UVDDA_42") (pintype "input"))
    )
    (net (code "55") (name "VCC_5V") (class "Default")
      (node (ref "C22") (pin "2") (pinfunction "2_2") (pintype "passive"))
      (node (ref "C29") (pin "2") (pinfunction "A_2") (pintype "passive"))
      (node (ref "C30") (pin "2") (pinfunction "2_2") (pintype "passive"))
      (node (ref "C32") (pin "2") (pinfunction "2_2") (pintype "passive"))
      (node (ref "D2") (pin "5") (pinfunction "VBUS_5") (pintype "passive"))
      (node (ref "D3") (pin "5") (pinfunction "VBUS_5") (pintype "passive"))
      (node (ref "F1") (pin "1") (pinfunction "1_1") (pintype "passive"))
      (node (ref "J2") (pin "A4") (pinfunction "VBUS_A4") (pintype "passive"))
      (node (ref "J2") (pin "A9") (pinfunction "VBUS_A9") (pintype "passive"))
      (node (ref "J3") (pin "22") (pinfunction "22_22") (pintype "passive"))
      (node (ref "J3") (pin "24") (pinfunction "24_24") (pintype "passive"))
      (node (ref "J4") (pin "4") (pinfunction "4_4") (pintype "passive"))
      (node (ref "J5") (pin "A9") (pinfunction "VBUS_A9") (pintype "passive"))
      (node (ref "R15") (pin "1") (pinfunction "1_1") (pintype "passive"))
      (node (ref "U2") (pin "3") (pinfunction "VIN_3") (pintype "power_in"))
      (node (ref "U3") (pin "4") (pinfunction "VCC_4") (pintype "power_in"))
    )
    (net (code "56") (name "VCC_A1") (class "Default")
      (node (ref "C17") (pin "2") (pinfunction "2_2") (pintype "passive"))
      (node (ref "C18") (pin "2") (pinfunction "2_2") (pintype "passive"))
      (node (ref "C28") (pin "1") (pinfunction "1_1") (pintype "passive"))
      (node (ref "FB1") (pin "2") (pinfunction "2_2") (pintype "passive"))
      (node (ref "U5") (pin "44") (pinfunction "VDDA_44") (pintype "input"))
      (node (ref "U5") (pin "46") (pinfunction "VCMI_46") (pintype "input"))
      (node (ref "U5") (pin "47") (pinfunction "VDDA_47") (pintype "input"))
    )
    (net (code "57") (name "VCC_PLL") (class "Default")
      (node (ref "C19") (pin "2") (pinfunction "2_2") (pintype "passive"))
      (node (ref "C20") (pin "2") (pinfunction "2_2") (pintype "passive"))
      (node (ref "FB2") (pin "2") (pinfunction "2_2") (pintype "passive"))
      (node (ref "U5") (pin "7") (pinfunction "VDDPLL_7") (pintype "input"))
    )
    (net (code "58") (name "unconnected-(ANT1-Support_Pad-Pad2)") (class "Default")
      (node (ref "ANT1") (pin "2") (pinfunction "Support_Pad_2") (pintype "passive"))
    )
    (net (code "59") (name "unconnected-(J2A-RX2+-PadA11)") (class "Default")
      (node (ref "J2") (pin "A11") (pinfunction "RX2+_A11") (pintype "passive"))
    )
    (net (code "60") (name "unconnected-(J2A-RX2--PadA10)") (class "Default")
      (node (ref "J2") (pin "A10") (pinfunction "RX2-_A10") (pintype "passive"))
    )
    (net (code "61") (name "unconnected-(J2A-SBU1-PadA8)") (class "Default")
      (node (ref "J2") (pin "A8") (pinfunction "SBU1_A8") (pintype "passive"))
    )
    (net (code "62") (name "unconnected-(J2A-TX1+-PadA2)") (class "Default")
      (node (ref "J2") (pin "A2") (pinfunction "TX1+_A2") (pintype "passive"))
    )
    (net (code "63") (name "unconnected-(J2A-TX1--PadA3)") (class "Default")
      (node (ref "J2") (pin "A3") (pinfunction "TX1-_A3") (pintype "passive"))
    )
    (net (code "64") (name "unconnected-(J3-Pad1)") (class "Default")
      (node (ref "J3") (pin "1") (pinfunction "1_1") (pintype "passive"))
    )
    (net (code "65") (name "unconnected-(J3-Pad2)") (class "Default")
      (node (ref "J3") (pin "2") (pinfunction "2_2") (pintype "passive"))
    )
    (net (code "66") (name "unconnected-(J3-Pad3)") (class "Default")
      (node (ref "J3") (pin "3") (pinfunction "3_3") (pintype "passive"))
    )
    (net (code "67") (name "unconnected-(J3-Pad4)") (class "Default")
      (node (ref "J3") (pin "4") (pinfunction "4_4") (pintype "passive"))
    )
    (net (code "68") (name "unconnected-(J3-Pad5)") (class "Default")
      (node (ref "J3") (pin "5") (pinfunction "5_5") (pintype "passive"))
    )
    (net (code "69") (name "unconnected-(J3-Pad7)") (class "Default")
      (node (ref "J3") (pin "7") (pinfunction "7_7") (pintype "passive"))
    )
    (net (code "70") (name "unconnected-(J3-Pad8)") (class "Default")
      (node (ref "J3") (pin "8") (pinfunction "8_8") (pintype "passive"))
    )
    (net (code "71") (name "unconnected-(J3-Pad9)") (class "Default")
      (node (ref "J3") (pin "9") (pinfunction "9_9") (pintype "passive"))
    )
    (net (code "72") (name "unconnected-(J3-Pad10)") (class "Default")
      (node (ref "J3") (pin "10") (pinfunction "10_10") (pintype "passive"))
    )
    (net (code "73") (name "unconnected-(J3-Pad11)") (class "Default")
      (node (ref "J3") (pin "11") (pinfunction "11_11") (pintype "passive"))
    )
    (net (code "74") (name "unconnected-(J3-Pad13)") (class "Default")
      (node (ref "J3") (pin "13") (pinfunction "13_13") (pintype "passive"))
    )
    (net (code "75") (name "unconnected-(J3-Pad14)") (class "Default")
      (node (ref "J3") (pin "14") (pinfunction "14_14") (pintype "passive"))
    )
    (net (code "76") (name "unconnected-(J3-Pad16)") (class "Default")
      (node (ref "J3") (pin "16") (pinfunction "16_16") (pintype "passive"))
    )
    (net (code "77") (name "unconnected-(J3-Pad17)") (class "Default")
      (node (ref "J3") (pin "17") (pinfunction "17_17") (pintype "passive"))
    )
    (net (code "78") (name "unconnected-(J3-Pad18)") (class "Default")
      (node (ref "J3") (pin "18") (pinfunction "18_18") (pintype "passive"))
    )
    (net (code "79") (name "unconnected-(J3-Pad19)") (class "Default")
      (node (ref "J3") (pin "19") (pinfunction "19_19") (pintype "passive"))
    )
    (net (code "80") (name "unconnected-(J3-Pad21)") (class "Default")
      (node (ref "J3") (pin "21") (pinfunction "21_21") (pintype "passive"))
    )
    (net (code "81") (name "unconnected-(J3-Pad23)") (class "Default")
      (node (ref "J3") (pin "23") (pinfunction "23_23") (pintype "passive"))
    )
    (net (code "82") (name "unconnected-(J4-Pad3)") (class "Default")
      (node (ref "J4") (pin "3") (pinfunction "3_3") (pintype "passive"))
    )
    (net (code "83") (name "unconnected-(J4-Pad5)") (class "Default")
      (node (ref "J4") (pin "5") (pinfunction "5_5") (pintype "passive"))
    )
    (net (code "84") (name "unconnected-(J4-Pad7)") (class "Default")
      (node (ref "J4") (pin "7") (pinfunction "7_7") (pintype "passive"))
    )
    (net (code "85") (name "unconnected-(J4-Pad9)") (class "Default")
      (node (ref "J4") (pin "9") (pinfunction "9_9") (pintype "passive"))
    )
    (net (code "86") (name "unconnected-(J4-Pad10)") (class "Default")
      (node (ref "J4") (pin "10") (pinfunction "10_10") (pintype "passive"))
    )
    (net (code "87") (name "unconnected-(J4-Pad11)") (class "Default")
      (node (ref "J4") (pin "11") (pinfunction "11_11") (pintype "passive"))
    )
    (net (code "88") (name "unconnected-(J4-Pad12)") (class "Default")
      (node (ref "J4") (pin "12") (pinfunction "12_12") (pintype "passive"))
    )
    (net (code "89") (name "unconnected-(J4-Pad13)") (class "Default")
      (node (ref "J4") (pin "13") (pinfunction "13_13") (pintype "passive"))
    )
    (net (code "90") (name "unconnected-(J4-Pad14)") (class "Default")
      (node (ref "J4") (pin "14") (pinfunction "14_14") (pintype "passive"))
    )
    (net (code "91") (name "unconnected-(J4-Pad16)") (class "Default")
      (node (ref "J4") (pin "16") (pinfunction "16_16") (pintype "passive"))
    )
    (net (code "92") (name "unconnected-(J4-Pad18)") (class "Default")
      (node (ref "J4") (pin "18") (pinfunction "18_18") (pintype "passive"))
    )
    (net (code "93") (name "unconnected-(J4-Pad20)") (class "Default")
      (node (ref "J4") (pin "20") (pinfunction "20_20") (pintype "passive"))
    )
    (net (code "94") (name "unconnected-(J4-Pad22)") (class "Default")
      (node (ref "J4") (pin "22") (pinfunction "22_22") (pintype "passive"))
    )
    (net (code "95") (name "unconnected-(J4-Pad23)") (class "Default")
      (node (ref "J4") (pin "23") (pinfunction "23_23") (pintype "passive"))
    )
    (net (code "96") (name "unconnected-(J4-Pad24)") (class "Default")
      (node (ref "J4") (pin "24") (pinfunction "24_24") (pintype "passive"))
    )
    (net (code "97") (name "unconnected-(J5A-RX2+-PadA11)") (class "Default")
      (node (ref "J5") (pin "A11") (pinfunction "RX2+_A11") (pintype "passive"))
    )
    (net (code "98") (name "unconnected-(J5A-RX2--PadA10)") (class "Default")
      (node (ref "J5") (pin "A10") (pinfunction "RX2-_A10") (pintype "passive"))
    )
    (net (code "99") (name "unconnected-(J5A-SBU1-PadA8)") (class "Default")
      (node (ref "J5") (pin "A8") (pinfunction "SBU1_A8") (pintype "passive"))
    )
    (net (code "100") (name "unconnected-(J5A-TX1+-PadA2)") (class "Default")
      (node (ref "J5") (pin "A2") (pinfunction "TX1+_A2") (pintype "passive"))
    )
    (net (code "101") (name "unconnected-(J5A-TX1--PadA3)") (class "Default")
      (node (ref "J5") (pin "A3") (pinfunction "TX1-_A3") (pintype "passive"))
    )
    (net (code "102") (name "unconnected-(J5A-VBUS-PadA4)") (class "Default")
      (node (ref "J5") (pin "A4") (pinfunction "VBUS_A4") (pintype "passive"))
    )
    (net (code "103") (name "unconnected-(U1-LT-Pad3)") (class "Default")
      (node (ref "U1") (pin "3") (pinfunction "LT_3") (pintype "passive"))
    )
    (net (code "104") (name "unconnected-(U1-NC-Pad1)") (class "Default")
      (node (ref "U1") (pin "1") (pinfunction "NC_1") (pintype "passive"))
    )
    (net (code "105") (name "unconnected-(U3-CBUS0-Pad6)") (class "Default")
      (node (ref "U3") (pin "6") (pinfunction "CBUS0_6") (pintype "bidirectional"))
    )
    (net (code "106") (name "unconnected-(U3-VCCIO-Pad9)") (class "Default")
      (node (ref "U3") (pin "9") (pinfunction "VCCIO_9") (pintype "power_in"))
    )
    (net (code "107") (name "unconnected-(U3-~{CTS}-Pad11)") (class "Default")
      (node (ref "U3") (pin "11") (pinfunction "~{CTS}_11") (pintype "input"))
    )
    (net (code "108") (name "unconnected-(U3-~{RTS}-Pad8)") (class "Default")
      (node (ref "U3") (pin "8") (pinfunction "~{RTS}_8") (pintype "input"))
    )
    (net (code "109") (name "unconnected-(U4-~{WC}-Pad7)") (class "Default")
      (node (ref "U4") (pin "7") (pinfunction "~{WC}_7") (pintype "input"))
    )
    (net (code "110") (name "unconnected-(U5-AGC_RF-Pad15)") (class "Default")
      (node (ref "U5") (pin "15") (pinfunction "AGC_RF_15") (pintype "input"))
    )
    (net (code "111") (name "unconnected-(U5-GPIO0-Pad37)") (class "Default")
      (node (ref "U5") (pin "37") (pinfunction "GPIO0_37") (pintype "input"))
    )
    (net (code "112") (name "unconnected-(U5-GPIO1-Pad32)") (class "Default")
      (node (ref "U5") (pin "32") (pinfunction "GPIO1_32") (pintype "input"))
    )
    (net (code "113") (name "unconnected-(U5-GPIO2-Pad31)") (class "Default")
      (node (ref "U5") (pin "31") (pinfunction "GPIO2_31") (pintype "input"))
    )
    (net (code "114") (name "unconnected-(U5-GPIO3-Pad36)") (class "Default")
      (node (ref "U5") (pin "36") (pinfunction "GPIO3_36") (pintype "input"))
    )
    (net (code "115") (name "unconnected-(U5-GPIO4-Pad30)") (class "Default")
      (node (ref "U5") (pin "30") (pinfunction "GPIO4_30") (pintype "input"))
    )
    (net (code "116") (name "unconnected-(U5-GPIO5-Pad29)") (class "Default")
      (node (ref "U5") (pin "29") (pinfunction "GPIO5_29") (pintype "input"))
    )
    (net (code "117") (name "unconnected-(U5-GPIO6-Pad22)") (class "Default")
      (node (ref "U5") (pin "22") (pinfunction "GPIO6_22") (pintype "input"))
    )
    (net (code "118") (name "unconnected-(U5-GPIO7-Pad21)") (class "Default")
      (node (ref "U5") (pin "21") (pinfunction "GPIO7_21") (pintype "input"))
    )
    (net (code "119") (name "unconnected-(U5-IR_RX_IN-Pad38)") (class "Default")
      (node (ref "U5") (pin "38") (pinfunction "IR_RX_IN_38") (pintype "input"))
    )
    (net (code "120") (name "unconnected-(U5-M_ERR-Pad35)") (class "Default")
      (node (ref "U5") (pin "35") (pinfunction "M_ERR_35") (pintype "input"))
    )
    (net (code "121") (name "unconnected-(U5-TP_CKO-Pad9)") (class "Default")
      (node (ref "U5") (pin "9") (pinfunction "TP_CKO_9") (pintype "input"))
    )
    (net (code "122") (name "unconnected-(U5-VINR-Pad6)") (class "Default")
      (node (ref "U5") (pin "6") (pinfunction "VINR_6") (pintype "input"))
    )
    (net (code "123") (name "unconnected-(U5-VQN-Pad5)") (class "Default")
      (node (ref "U5") (pin "5") (pinfunction "VQN_5") (pintype "input"))
    )
    (net (code "124") (name "unconnected-(U5-VQP-Pad4)") (class "Default")
      (node (ref "U5") (pin "4") (pinfunction "VQP_4") (pintype "input"))
    )
  )
)
